# Memory_USB.net
KiCad netlist of a schematic drawn in Altium Designer
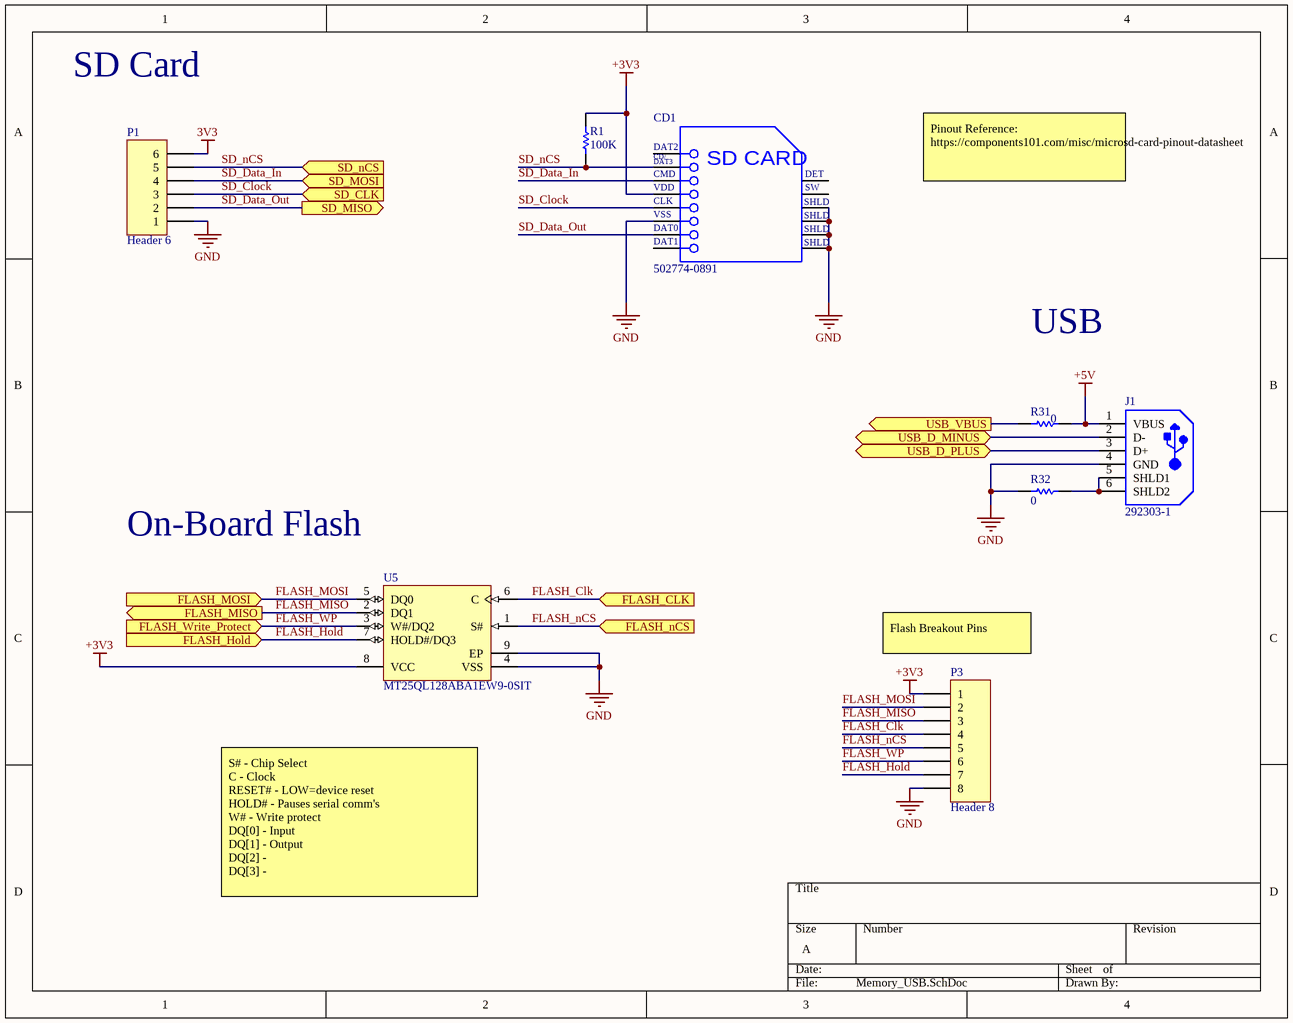
[diagram p0: Memory_USB.SchDoc]

(export (version "E")
  (design (tool "Eeschema 10.0.6"))
  (components
    (comp (ref "CD1")
      (value "502774-0891")
      (footprint "MOLX-502774-0891_V")
      (description "Micro SD Memory Card Connector, 0.5 A, 10 V (DC), -25 to 85 degC, 8-Pin SMT, RoHS, Tape and Reel")
      (fields (field (name "MANUFACTURER") "Molex"))
      (libsource (lib "Altium Content Vault") (part "CN-SD-8-2SW-4S_B"))
    )
    (comp (ref "J1")
      (value "292303-1")
      (footprint "TE-292303-1_V")
      (fields (field (name "MANUFACTURER") "TE Connectivity"))
      (libsource (lib "Altium Content Vault") (part "USB-4-2SHLD"))
    )
    (comp (ref "P1")
      (value "Header 6")
      (footprint "HDR1X6")
      (description "Header, 6-Pin")
      (fields (field (name "PUBLISHER") "Altium Limited"))
      (libsource (lib "Miscellaneous Connectors") (part "Header 6"))
    )
    (comp (ref "P3")
      (value "Header 8")
      (footprint "HDR1X8")
      (description "Header, 8-Pin")
      (fields (field (name "PUBLISHER") "Altium Limited"))
      (libsource (lib "Miscellaneous Connectors") (part "Header 8"))
    )
    (comp (ref "R1")
      (value "100K")
      (footprint "RESC1608X55X25ML10T15")
      (description "Chip Resistor, 100 KOhm, +/- 1%, 0.1 W, -55 to 155 degC, 0603 (1608 Metric), RoHS, Tape and Reel")
      (fields (field (name "MANUFACTURER") "Yageo") (field (name "TOLERANCE") "1%"))
      (libsource (lib "Altium Content Vault") (part "RES-2"))
    )
    (comp (ref "R31")
      (value "0")
      (footprint "RESC1608X55X25ML10T15")
      (description "Chip Resistor, 0 Ohm, +/- 5%, 0.1 W, -55 to 155 degC, 0603 (1608 Metric), RoHS, Tape and Reel")
      (fields (field (name "TOLERANCE") "5%") (field (name "MANUFACTURER") "Yageo"))
      (libsource (lib "Altium Content Vault") (part "RES-2"))
    )
    (comp (ref "R32")
      (value "0")
      (footprint "RESC1608X55X25ML10T15")
      (description "Chip Resistor, 0 Ohm, +/- 5%, 0.1 W, -55 to 155 degC, 0603 (1608 Metric), RoHS, Tape and Reel")
      (fields (field (name "TOLERANCE") "5%") (field (name "MANUFACTURER") "Yageo"))
      (libsource (lib "Altium Content Vault") (part "RES-2"))
    )
    (comp (ref "U5")
      (value "MT25QL128ABA1EW9-0SIT")
      (footprint "MICT-W9-8_L")
      (fields (field (name "MANUFACTURER") "Micron"))
      (libsource (lib "Altium Content Vault") (part "MICT-MT25QL128ABA-W9-8"))
    )
  )
  (nets
    (net (code "1") (name "+3V3") (class "Default")
      (node (ref "CD1") (pin "4") (pinfunction "VDD_4") (pintype "passive"))
      (node (ref "P3") (pin "1") (pinfunction "1_1") (pintype "passive"))
      (node (ref "R1") (pin "2") (pinfunction "2_2") (pintype "passive"))
      (node (ref "U5") (pin "8") (pinfunction "VCC_8") (pintype "power_in"))
    )
    (net (code "2") (name "+5V") (class "Default")
      (node (ref "J1") (pin "1") (pinfunction "VBUS_1") (pintype "passive"))
      (node (ref "R31") (pin "2") (pinfunction "2_2") (pintype "passive"))
    )
    (net (code "3") (name "/FLASH_Clk") (class "Default")
      (node (ref "P3") (pin "4") (pinfunction "4_4") (pintype "passive"))
      (node (ref "U5") (pin "6") (pinfunction "C_6") (pintype "input"))
    )
    (net (code "4") (name "/FLASH_Hold") (class "Default")
      (node (ref "P3") (pin "7") (pinfunction "7_7") (pintype "passive"))
      (node (ref "U5") (pin "7") (pinfunction "HOLD#/DQ3_7") (pintype "bidirectional"))
    )
    (net (code "5") (name "/FLASH_MISO") (class "Default")
      (node (ref "P3") (pin "3") (pinfunction "3_3") (pintype "passive"))
      (node (ref "U5") (pin "2") (pinfunction "DQ1_2") (pintype "bidirectional"))
    )
    (net (code "6") (name "/FLASH_MOSI") (class "Default")
      (node (ref "P3") (pin "2") (pinfunction "2_2") (pintype "passive"))
      (node (ref "U5") (pin "5") (pinfunction "DQ0_5") (pintype "bidirectional"))
    )
    (net (code "7") (name "/FLASH_WP") (class "Default")
      (node (ref "P3") (pin "6") (pinfunction "6_6") (pintype "passive"))
      (node (ref "U5") (pin "3") (pinfunction "W#/DQ2_3") (pintype "bidirectional"))
    )
    (net (code "8") (name "/FLASH_nCS") (class "Default")
      (node (ref "P3") (pin "5") (pinfunction "5_5") (pintype "passive"))
      (node (ref "U5") (pin "1") (pinfunction "S#_1") (pintype "input"))
    )
    (net (code "9") (name "/SD_Clock") (class "Default")
      (node (ref "CD1") (pin "5") (pinfunction "CLK_5") (pintype "passive"))
      (node (ref "P1") (pin "3") (pinfunction "3_3") (pintype "passive"))
    )
    (net (code "10") (name "/SD_Data_In") (class "Default")
      (node (ref "CD1") (pin "3") (pinfunction "CMD_3") (pintype "passive"))
      (node (ref "P1") (pin "4") (pinfunction "4_4") (pintype "passive"))
    )
    (net (code "11") (name "/SD_Data_Out") (class "Default")
      (node (ref "CD1") (pin "7") (pinfunction "DAT0_7") (pintype "passive"))
      (node (ref "P1") (pin "2") (pinfunction "2_2") (pintype "passive"))
    )
    (net (code "12") (name "/SD_nCS") (class "Default")
      (node (ref "CD1") (pin "2") (pinfunction "CD/DAT3_2") (pintype "passive"))
      (node (ref "P1") (pin "5") (pinfunction "5_5") (pintype "passive"))
      (node (ref "R1") (pin "1") (pinfunction "1_1") (pintype "passive"))
    )
    (net (code "13") (name "/USB_D_MINUS") (class "Default")
      (node (ref "J1") (pin "2") (pinfunction "D-_2") (pintype "passive"))
    )
    (net (code "14") (name "/USB_D_PLUS") (class "Default")
      (node (ref "J1") (pin "3") (pinfunction "D+_3") (pintype "passive"))
    )
    (net (code "15") (name "/USB_VBUS") (class "Default")
      (node (ref "R31") (pin "1") (pinfunction "1_1") (pintype "passive"))
    )
    (net (code "16") (name "3V3") (class "Default")
      (node (ref "P1") (pin "6") (pinfunction "6_6") (pintype "passive"))
    )
    (net (code "17") (name "GND") (class "Default")
      (node (ref "CD1") (pin "11") (pinfunction "SHLD_11") (pintype "passive"))
      (node (ref "CD1") (pin "12") (pinfunction "SHLD_12") (pintype "passive"))
      (node (ref "CD1") (pin "13") (pinfunction "SHLD_13") (pintype "passive"))
      (node (ref "CD1") (pin "14") (pinfunction "SHLD_14") (pintype "passive"))
      (node (ref "CD1") (pin "6") (pinfunction "VSS_6") (pintype "passive"))
      (node (ref "J1") (pin "4") (pinfunction "GND_4") (pintype "passive"))
      (node (ref "P1") (pin "1") (pinfunction "1_1") (pintype "passive"))
      (node (ref "P3") (pin "8") (pinfunction "8_8") (pintype "passive"))
      (node (ref "R32") (pin "1") (pinfunction "1_1") (pintype "passive"))
      (node (ref "U5") (pin "4") (pinfunction "VSS_4") (pintype "power_in"))
      (node (ref "U5") (pin "9") (pinfunction "EP_9") (pintype "passive"))
    )
    (net (code "18") (name "Net-(J1-SHLD1)") (class "Default")
      (node (ref "J1") (pin "5") (pinfunction "SHLD1_5") (pintype "passive"))
      (node (ref "J1") (pin "6") (pinfunction "SHLD2_6") (pintype "passive"))
      (node (ref "R32") (pin "2") (pinfunction "2_2") (pintype "passive"))
    )
    (net (code "19") (name "unconnected-(CD1-DAT1-Pad8)") (class "Default")
      (node (ref "CD1") (pin "8") (pinfunction "DAT1_8") (pintype "passive"))
    )
    (net (code "20") (name "unconnected-(CD1-DAT2-Pad1)") (class "Default")
      (node (ref "CD1") (pin "1") (pinfunction "DAT2_1") (pintype "passive"))
    )
    (net (code "21") (name "unconnected-(CD1-DETECT-Pad9)") (class "Default")
      (node (ref "CD1") (pin "9") (pinfunction "DETECT_9") (pintype "passive"))
    )
    (net (code "22") (name "unconnected-(CD1-SWITCH-Pad10)") (class "Default")
      (node (ref "CD1") (pin "10") (pinfunction "SWITCH_10") (pintype "passive"))
    )
  )
)
